# decoupling.net
KiCad netlist of a schematic drawn in Altium Designer
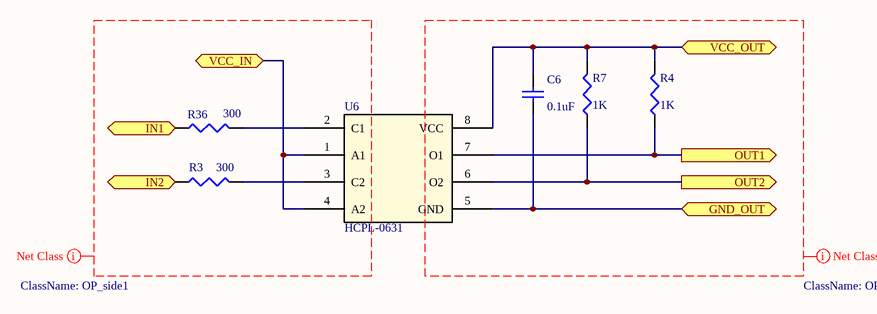
[diagram p0: decoupling.SchDoc]

(export (version "E")
  (design (tool "Eeschema 10.0.6"))
  (components
    (comp (ref "C6")
      (value "0.1uF")
      (footprint "C_0603")
      (description "Capacitor")
      (fields (field (name "Comment") "Cap") (field (name "PUBLISHER") "Altium Limited"))
      (libsource (lib "AX_Altium_v2.3") (part "Cap Semi"))
    )
    (comp (ref "R3")
      (value "300")
      (footprint "R_0603")
      (description "Resistor")
      (fields (field (name "Comment") "Res") (field (name "PUBLISHER") "Altium Limited"))
      (libsource (lib "AX_Altium_v2.3") (part "Res3"))
    )
    (comp (ref "R4")
      (value "1K")
      (footprint "R_0603")
      (description "Resistor")
      (fields (field (name "Comment") "Res") (field (name "PUBLISHER") "Altium Limited"))
      (libsource (lib "AX_Altium_v2.3") (part "Res3"))
    )
    (comp (ref "R7")
      (value "1K")
      (footprint "R_0603")
      (description "Resistor")
      (fields (field (name "Comment") "Res") (field (name "PUBLISHER") "Altium Limited"))
      (libsource (lib "AX_Altium_v2.3") (part "Res3"))
    )
    (comp (ref "R36")
      (value "300")
      (footprint "R_0603")
      (description "Resistor")
      (fields (field (name "Comment") "Res") (field (name "PUBLISHER") "Altium Limited"))
      (libsource (lib "AX_Altium_v2.3") (part "Res3"))
    )
    (comp (ref "U6")
      (value "HCPL-0631")
      (footprint "Miscellaneous Devices:SO8_M")
      (description "Optocoupler, dual")
      (libsource (lib "Add_lib") (part "HCPL-0631"))
    )
  )
  (nets
    (net (code "1") (name "/GND_OUT") (class "Default")
      (node (ref "C6") (pin "1") (pinfunction "1_1") (pintype "passive"))
      (node (ref "U6") (pin "5") (pinfunction "GND_5") (pintype "passive"))
    )
    (net (code "2") (name "/IN1") (class "Default")
      (node (ref "R36") (pin "1") (pinfunction "1_1") (pintype "passive"))
    )
    (net (code "3") (name "/IN2") (class "Default")
      (node (ref "R3") (pin "1") (pinfunction "1_1") (pintype "passive"))
    )
    (net (code "4") (name "/OUT1") (class "Default")
      (node (ref "R4") (pin "1") (pinfunction "1_1") (pintype "passive"))
      (node (ref "U6") (pin "7") (pinfunction "O1_7") (pintype "passive"))
    )
    (net (code "5") (name "/OUT2") (class "Default")
      (node (ref "R7") (pin "1") (pinfunction "1_1") (pintype "passive"))
      (node (ref "U6") (pin "6") (pinfunction "O2_6") (pintype "passive"))
    )
    (net (code "6") (name "/VCC_IN") (class "Default")
      (node (ref "U6") (pin "1") (pinfunction "A1_1") (pintype "passive"))
      (node (ref "U6") (pin "4") (pinfunction "A2_4") (pintype "passive"))
    )
    (net (code "7") (name "/VCC_OUT") (class "Default")
      (node (ref "C6") (pin "2") (pinfunction "2_2") (pintype "passive"))
      (node (ref "R4") (pin "2") (pinfunction "2_2") (pintype "passive"))
      (node (ref "R7") (pin "2") (pinfunction "2_2") (pintype "passive"))
      (node (ref "U6") (pin "8") (pinfunction "VCC_8") (pintype "passive"))
    )
    (net (code "8") (name "Net-(U6-C1)") (class "Default")
      (node (ref "R36") (pin "2") (pinfunction "2_2") (pintype "passive"))
      (node (ref "U6") (pin "2") (pinfunction "C1_2") (pintype "passive"))
    )
    (net (code "9") (name "Net-(U6-C2)") (class "Default")
      (node (ref "R3") (pin "2") (pinfunction "2_2") (pintype "passive"))
      (node (ref "U6") (pin "3") (pinfunction "C2_3") (pintype "passive"))
    )
  )
)
